# DiverInterfaceBoard.net
KiCad netlist of a schematic drawn in Altium Designer
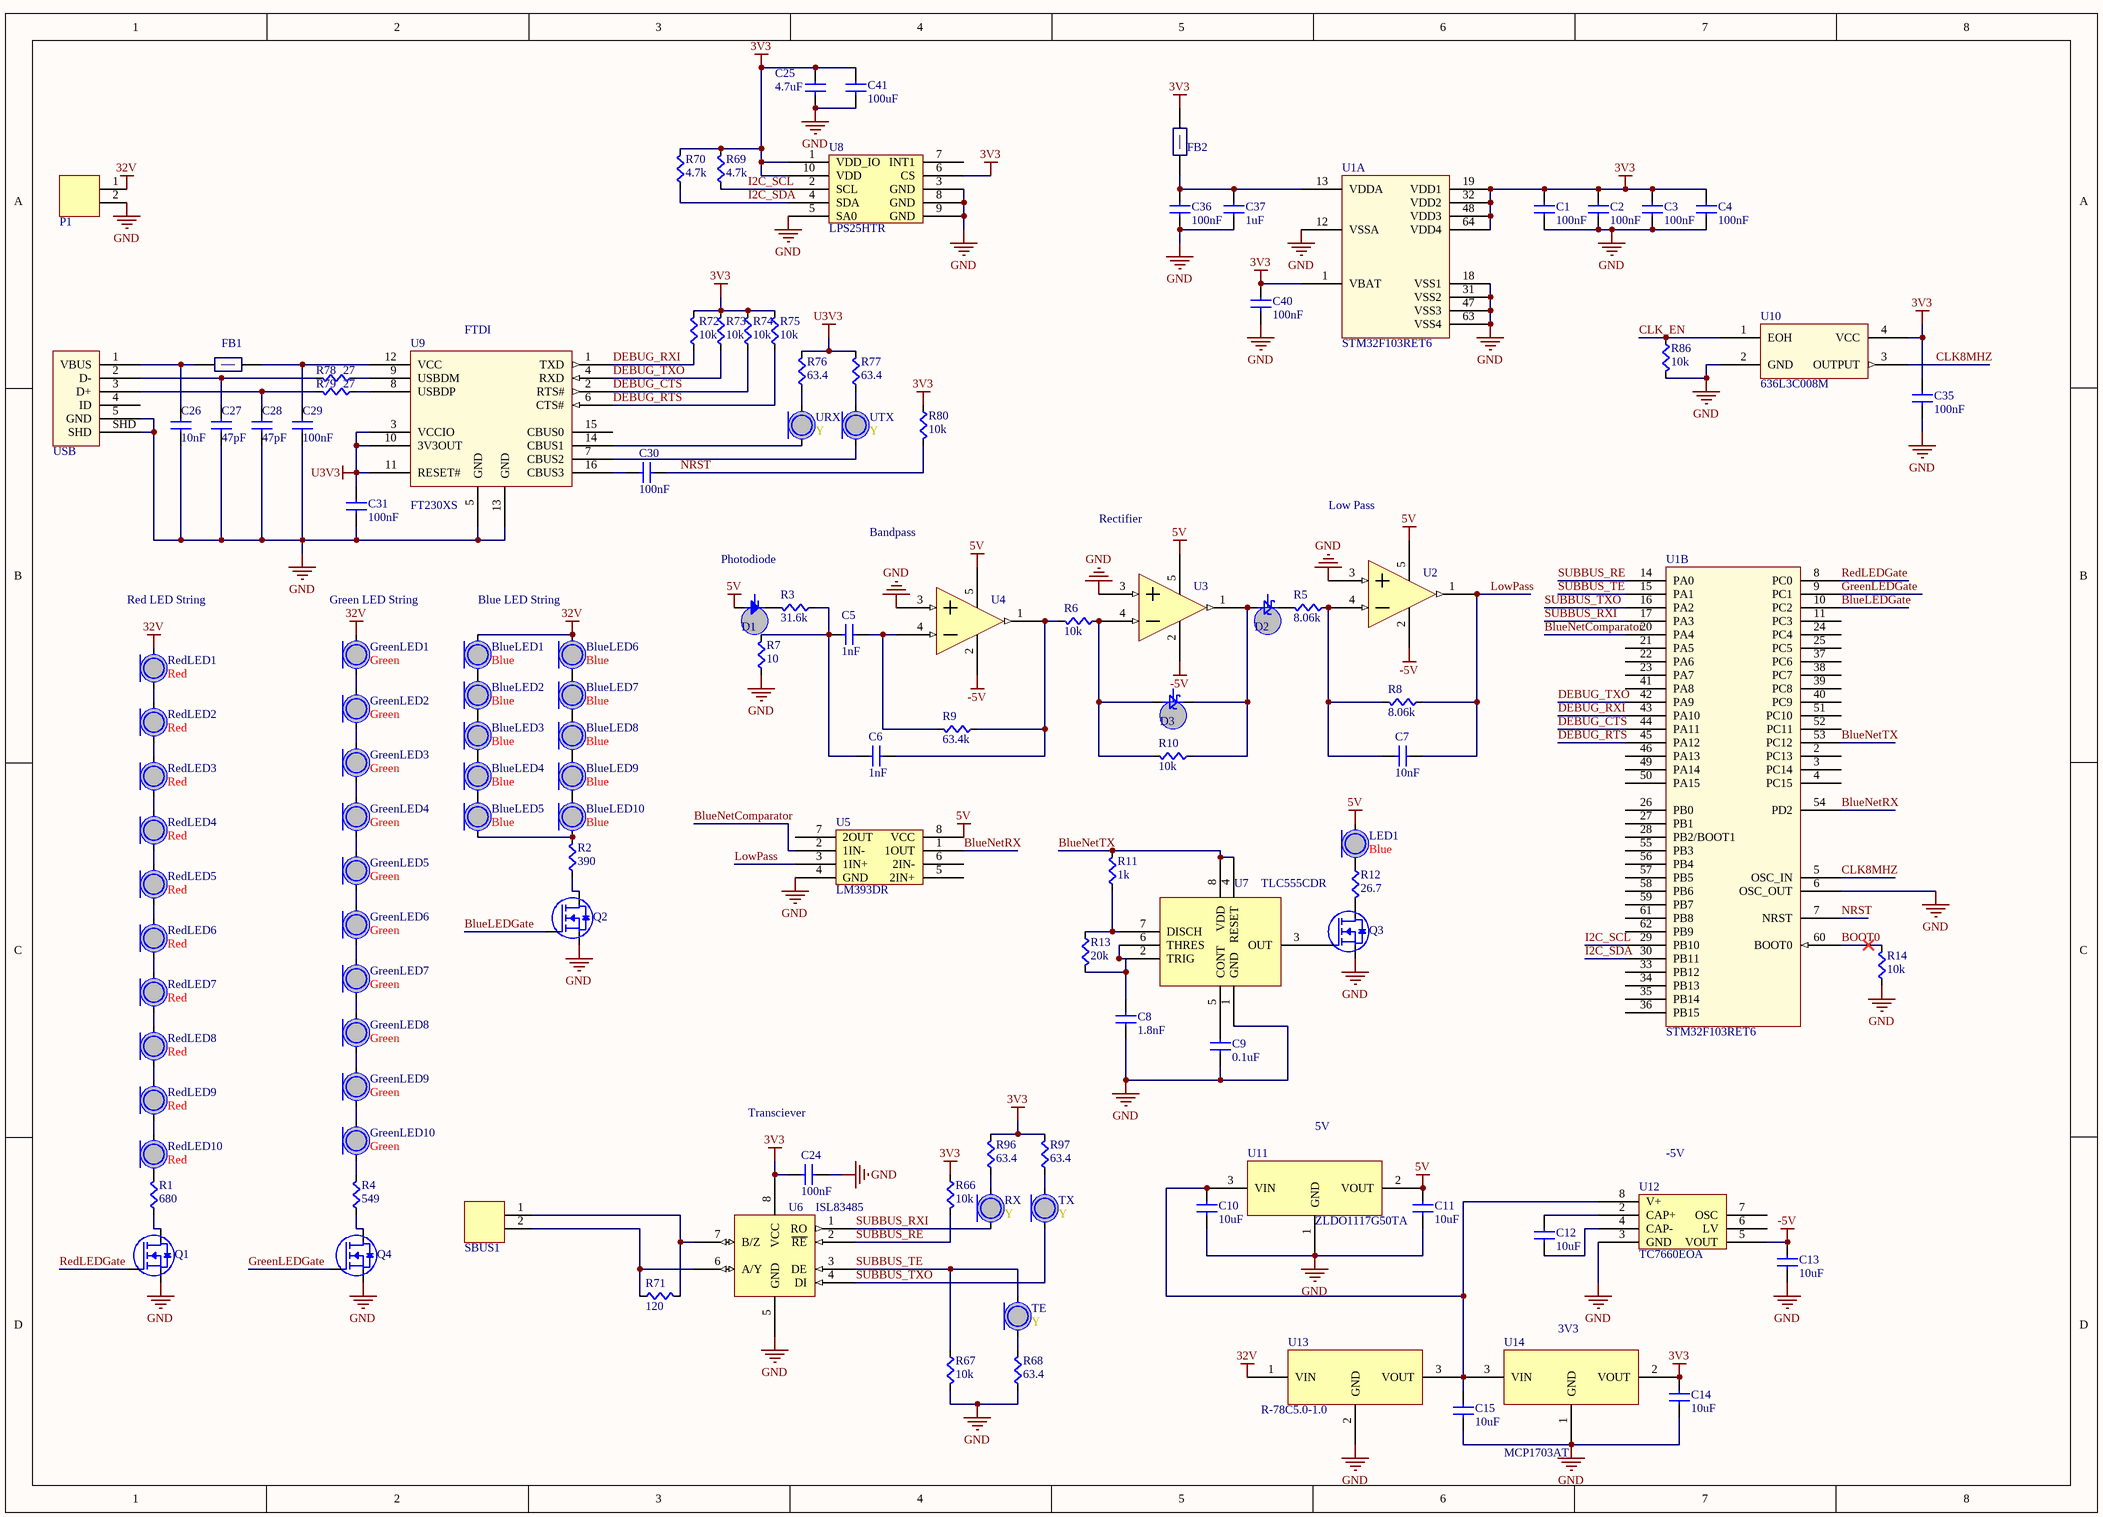
[diagram p0: DiverInterfaceBoard.SchDoc]

(export (version "E")
  (design (tool "Eeschema 10.0.6"))
  (components
    (comp (ref "BlueLED1")
      (value "LED")
      (footprint "LED1206")
      (fields (field (name "COLOR") "Blue"))
      (libsource (lib "SubjuGator8") (part "LED"))
    )
    (comp (ref "BlueLED2")
      (value "LED")
      (footprint "LED1206")
      (fields (field (name "COLOR") "Blue"))
      (libsource (lib "SubjuGator8") (part "LED"))
    )
    (comp (ref "BlueLED3")
      (value "LED")
      (footprint "LED1206")
      (fields (field (name "COLOR") "Blue"))
      (libsource (lib "SubjuGator8") (part "LED"))
    )
    (comp (ref "BlueLED4")
      (value "LED")
      (footprint "LED1206")
      (fields (field (name "COLOR") "Blue"))
      (libsource (lib "SubjuGator8") (part "LED"))
    )
    (comp (ref "BlueLED5")
      (value "LED")
      (footprint "LED1206")
      (fields (field (name "COLOR") "Blue"))
      (libsource (lib "SubjuGator8") (part "LED"))
    )
    (comp (ref "BlueLED6")
      (value "LED")
      (footprint "LED1206")
      (fields (field (name "COLOR") "Blue"))
      (libsource (lib "SubjuGator8") (part "LED"))
    )
    (comp (ref "BlueLED7")
      (value "LED")
      (footprint "LED1206")
      (fields (field (name "COLOR") "Blue"))
      (libsource (lib "SubjuGator8") (part "LED"))
    )
    (comp (ref "BlueLED8")
      (value "LED")
      (footprint "LED1206")
      (fields (field (name "COLOR") "Blue"))
      (libsource (lib "SubjuGator8") (part "LED"))
    )
    (comp (ref "BlueLED9")
      (value "LED")
      (footprint "LED1206")
      (fields (field (name "COLOR") "Blue"))
      (libsource (lib "SubjuGator8") (part "LED"))
    )
    (comp (ref "BlueLED10")
      (value "LED")
      (footprint "LED1206")
      (fields (field (name "COLOR") "Blue"))
      (libsource (lib "SubjuGator8") (part "LED"))
    )
    (comp (ref "C1")
      (value "100nF")
      (footprint "CAPC0603")
      (fields (field (name "Comment") "Cap"))
      (libsource (lib "SubjuGator8") (part "Cap"))
    )
    (comp (ref "C2")
      (value "100nF")
      (footprint "CAPC0603")
      (fields (field (name "Comment") "Cap"))
      (libsource (lib "SubjuGator8") (part "Cap"))
    )
    (comp (ref "C3")
      (value "100nF")
      (footprint "CAPC0603")
      (fields (field (name "Comment") "Cap"))
      (libsource (lib "SubjuGator8") (part "Cap"))
    )
    (comp (ref "C4")
      (value "100nF")
      (footprint "CAPC0603")
      (fields (field (name "Comment") "Cap"))
      (libsource (lib "SubjuGator8") (part "Cap"))
    )
    (comp (ref "C5")
      (value "1nF")
      (footprint "CAPC0603")
      (fields (field (name "Comment") "Cap"))
      (libsource (lib "SubjuGator8") (part "Cap"))
    )
    (comp (ref "C6")
      (value "1nF")
      (footprint "CAPC0603")
      (fields (field (name "Comment") "Cap"))
      (libsource (lib "SubjuGator8") (part "Cap"))
    )
    (comp (ref "C7")
      (value "10nF")
      (footprint "CAPC0603")
      (fields (field (name "Comment") "Cap"))
      (libsource (lib "SubjuGator8") (part "Cap"))
    )
    (comp (ref "C8")
      (value "1.8nF")
      (footprint "CAPC0603")
      (fields (field (name "Comment") "Cap"))
      (libsource (lib "SubjuGator8") (part "Cap"))
    )
    (comp (ref "C9")
      (value "0.1uF")
      (footprint "CAPC0603")
      (fields (field (name "Comment") "Cap"))
      (libsource (lib "SubjuGator8") (part "Cap"))
    )
    (comp (ref "C10")
      (value "10uF")
      (footprint "CAPC0603")
      (fields (field (name "Comment") "Cap"))
      (libsource (lib "SubjuGator8") (part "Cap"))
    )
    (comp (ref "C11")
      (value "10uF")
      (footprint "CAPC0603")
      (fields (field (name "Comment") "Cap"))
      (libsource (lib "SubjuGator8") (part "Cap"))
    )
    (comp (ref "C12")
      (value "10uF")
      (footprint "CAPC0603")
      (fields (field (name "Comment") "Cap"))
      (libsource (lib "SubjuGator8") (part "Cap"))
    )
    (comp (ref "C13")
      (value "10uF")
      (footprint "CAPC0603")
      (fields (field (name "Comment") "Cap"))
      (libsource (lib "SubjuGator8") (part "Cap"))
    )
    (comp (ref "C14")
      (value "10uF")
      (footprint "CAPC0603")
      (fields (field (name "Comment") "Cap"))
      (libsource (lib "SubjuGator8") (part "Cap"))
    )
    (comp (ref "C15")
      (value "10uF")
      (footprint "CAPC0603")
      (fields (field (name "Comment") "Cap"))
      (libsource (lib "SubjuGator8") (part "Cap"))
    )
    (comp (ref "C24")
      (value "100nF")
      (footprint "CAPC0603")
      (fields (field (name "Comment") "Cap"))
      (libsource (lib "SubjuGator8") (part "Cap"))
    )
    (comp (ref "C25")
      (value "4.7uF")
      (footprint "CAPC0603")
      (fields (field (name "Comment") "Cap"))
      (libsource (lib "SubjuGator8") (part "Cap"))
    )
    (comp (ref "C26")
      (value "10nF")
      (footprint "CAPC0603")
      (fields (field (name "Comment") "Cap"))
      (libsource (lib "SubjuGator8") (part "Cap"))
    )
    (comp (ref "C27")
      (value "47pF")
      (footprint "CAPC0603")
      (fields (field (name "Comment") "Cap"))
      (libsource (lib "SubjuGator8") (part "Cap"))
    )
    (comp (ref "C28")
      (value "47pF")
      (footprint "CAPC0603")
      (fields (field (name "Comment") "Cap"))
      (libsource (lib "SubjuGator8") (part "Cap"))
    )
    (comp (ref "C29")
      (value "100nF")
      (footprint "CAPC0603")
      (fields (field (name "Comment") "Cap"))
      (libsource (lib "SubjuGator8") (part "Cap"))
    )
    (comp (ref "C30")
      (value "100nF")
      (footprint "CAPC0603")
      (fields (field (name "Comment") "Cap"))
      (libsource (lib "SubjuGator8") (part "Cap"))
    )
    (comp (ref "C31")
      (value "100nF")
      (footprint "CAPC0603")
      (fields (field (name "Comment") "Cap"))
      (libsource (lib "SubjuGator8") (part "Cap"))
    )
    (comp (ref "C35")
      (value "100nF")
      (footprint "CAPC0603")
      (fields (field (name "Comment") "Cap"))
      (libsource (lib "SubjuGator8") (part "Cap"))
    )
    (comp (ref "C36")
      (value "100nF")
      (footprint "CAPC0603")
      (fields (field (name "Comment") "Cap"))
      (libsource (lib "SubjuGator8") (part "Cap"))
    )
    (comp (ref "C37")
      (value "1uF")
      (footprint "CAPC0603")
      (fields (field (name "Comment") "Cap"))
      (libsource (lib "SubjuGator8") (part "Cap"))
    )
    (comp (ref "C40")
      (value "100nF")
      (footprint "CAPC0603")
      (fields (field (name "MANUFACTURER") "Kemet") (field (name "Comment") "Cap"))
      (libsource (lib "SubjuGator8") (part "Cap"))
    )
    (comp (ref "C41")
      (value "100uF")
      (footprint "CAPC1206")
      (fields (field (name "Comment") "Cap"))
      (libsource (lib "SubjuGator8") (part "Cap"))
    )
    (comp (ref "D1")
      (value "Diode")
      (footprint "TEMD5510FX01")
      (description "Standard Diode Template")
      (libsource (lib "SubjuGator8") (part "Diode"))
    )
    (comp (ref "D2")
      (value "Schottky")
      (footprint "1N5819HW-7-F")
      (description "Schottky Diode Template")
      (libsource (lib "SubjuGator8") (part "Schottky"))
    )
    (comp (ref "D3")
      (value "Schottky")
      (footprint "1N5819HW-7-F")
      (description "Schottky Diode Template")
      (libsource (lib "SubjuGator8") (part "Schottky"))
    )
    (comp (ref "FB1")
      (value "FBead")
      (footprint "RES0603")
      (description "Ferrite Bead")
      (libsource (lib "SubjuGator8") (part "FBead"))
    )
    (comp (ref "FB2")
      (value "FBead")
      (footprint "RES0603")
      (description "Ferrite Bead")
      (libsource (lib "") (part "FBead_1"))
    )
    (comp (ref "GreenLED1")
      (value "LED")
      (footprint "LED1206")
      (fields (field (name "COLOR") "Green"))
      (libsource (lib "SubjuGator8") (part "LED"))
    )
    (comp (ref "GreenLED2")
      (value "LED")
      (footprint "LED1206")
      (fields (field (name "COLOR") "Green"))
      (libsource (lib "SubjuGator8") (part "LED"))
    )
    (comp (ref "GreenLED3")
      (value "LED")
      (footprint "LED1206")
      (fields (field (name "COLOR") "Green"))
      (libsource (lib "SubjuGator8") (part "LED"))
    )
    (comp (ref "GreenLED4")
      (value "LED")
      (footprint "LED1206")
      (fields (field (name "COLOR") "Green"))
      (libsource (lib "SubjuGator8") (part "LED"))
    )
    (comp (ref "GreenLED5")
      (value "LED")
      (footprint "LED1206")
      (fields (field (name "COLOR") "Green"))
      (libsource (lib "SubjuGator8") (part "LED"))
    )
    (comp (ref "GreenLED6")
      (value "LED")
      (footprint "LED1206")
      (fields (field (name "COLOR") "Green"))
      (libsource (lib "SubjuGator8") (part "LED"))
    )
    (comp (ref "GreenLED7")
      (value "LED")
      (footprint "LED1206")
      (fields (field (name "COLOR") "Green"))
      (libsource (lib "SubjuGator8") (part "LED"))
    )
    (comp (ref "GreenLED8")
      (value "LED")
      (footprint "LED1206")
      (fields (field (name "COLOR") "Green"))
      (libsource (lib "SubjuGator8") (part "LED"))
    )
    (comp (ref "GreenLED9")
      (value "LED")
      (footprint "LED1206")
      (fields (field (name "COLOR") "Green"))
      (libsource (lib "SubjuGator8") (part "LED"))
    )
    (comp (ref "GreenLED10")
      (value "LED")
      (footprint "LED1206")
      (fields (field (name "COLOR") "Green"))
      (libsource (lib "SubjuGator8") (part "LED"))
    )
    (comp (ref "LED1")
      (value "LED")
      (footprint "LED0603")
      (fields (field (name "COLOR") "Blue"))
      (libsource (lib "SubjuGator8") (part "LED"))
    )
    (comp (ref "P1")
      (value "2-pin Vert Sherlock")
      (footprint "MOLEX-HDR-1X2-SHERLOCK-VERT")
      (libsource (lib "SubjuGator8") (part "MOLEX-HDR-1x2-SHERLOCK_VERT"))
    )
    (comp (ref "Q1")
      (value "FDN5630")
      (footprint "PowerSOT-3")
      (description "60V N-Channel PowerTrench MOSFET")
      (libsource (lib "SubjuGator8") (part "FDN5630"))
    )
    (comp (ref "Q2")
      (value "FDN5630")
      (footprint "PowerSOT-3")
      (description "60V N-Channel PowerTrench MOSFET")
      (libsource (lib "SubjuGator8") (part "FDN5630"))
    )
    (comp (ref "Q3")
      (value "FDN5630")
      (footprint "PowerSOT-3")
      (description "60V N-Channel PowerTrench MOSFET")
      (libsource (lib "SubjuGator8") (part "FDN5630"))
    )
    (comp (ref "Q4")
      (value "FDN5630")
      (footprint "PowerSOT-3")
      (description "60V N-Channel PowerTrench MOSFET")
      (libsource (lib "SubjuGator8") (part "FDN5630"))
    )
    (comp (ref "R1")
      (value "680")
      (footprint "RES0603")
      (fields (field (name "Comment") "Res"))
      (libsource (lib "SubjuGator8") (part "Res"))
    )
    (comp (ref "R2")
      (value "390")
      (footprint "RES0603")
      (fields (field (name "Comment") "Res"))
      (libsource (lib "SubjuGator8") (part "Res"))
    )
    (comp (ref "R3")
      (value "31.6k")
      (footprint "RES0603")
      (fields (field (name "Comment") "Res"))
      (libsource (lib "SubjuGator8") (part "Res"))
    )
    (comp (ref "R4")
      (value "549")
      (footprint "RES0603")
      (fields (field (name "Comment") "Res"))
      (libsource (lib "SubjuGator8") (part "Res"))
    )
    (comp (ref "R5")
      (value "8.06k")
      (footprint "RES0603")
      (fields (field (name "Comment") "Res"))
      (libsource (lib "SubjuGator8") (part "Res"))
    )
    (comp (ref "R6")
      (value "10k")
      (footprint "RES0603")
      (fields (field (name "Comment") "Res"))
      (libsource (lib "SubjuGator8") (part "Res"))
    )
    (comp (ref "R7")
      (value "10")
      (footprint "RES0603")
      (fields (field (name "Comment") "Res"))
      (libsource (lib "SubjuGator8") (part "Res"))
    )
    (comp (ref "R8")
      (value "8.06k")
      (footprint "RES0603")
      (fields (field (name "Comment") "Res"))
      (libsource (lib "SubjuGator8") (part "Res"))
    )
    (comp (ref "R9")
      (value "63.4k")
      (footprint "RES0603")
      (fields (field (name "Comment") "Res"))
      (libsource (lib "SubjuGator8") (part "Res"))
    )
    (comp (ref "R10")
      (value "10k")
      (footprint "RES0603")
      (fields (field (name "Comment") "Res"))
      (libsource (lib "SubjuGator8") (part "Res"))
    )
    (comp (ref "R11")
      (value "1k")
      (footprint "RES0603")
      (fields (field (name "Comment") "Res"))
      (libsource (lib "SubjuGator8") (part "Res"))
    )
    (comp (ref "R12")
      (value "26.7")
      (footprint "RES0603")
      (fields (field (name "Comment") "Res"))
      (libsource (lib "SubjuGator8") (part "Res"))
    )
    (comp (ref "R13")
      (value "20k")
      (footprint "RES0603")
      (fields (field (name "Comment") "Res"))
      (libsource (lib "SubjuGator8") (part "Res"))
    )
    (comp (ref "R14")
      (value "10k")
      (footprint "RES0603")
      (fields (field (name "Comment") "Res"))
      (libsource (lib "SubjuGator8") (part "Res"))
    )
    (comp (ref "R66")
      (value "10k")
      (footprint "RES0603")
      (fields (field (name "Comment") "Res"))
      (libsource (lib "SubjuGator8") (part "Res"))
    )
    (comp (ref "R67")
      (value "10k")
      (footprint "RES0603")
      (fields (field (name "Comment") "Res"))
      (libsource (lib "SubjuGator8") (part "Res"))
    )
    (comp (ref "R68")
      (value "63.4")
      (footprint "RES0603")
      (fields (field (name "Comment") "Res"))
      (libsource (lib "SubjuGator8") (part "Res"))
    )
    (comp (ref "R69")
      (value "4.7k")
      (footprint "RES0603")
      (fields (field (name "Comment") "Res"))
      (libsource (lib "SubjuGator8") (part "Res"))
    )
    (comp (ref "R70")
      (value "4.7k")
      (footprint "RES0603")
      (fields (field (name "Comment") "Res"))
      (libsource (lib "SubjuGator8") (part "Res"))
    )
    (comp (ref "R71")
      (value "120")
      (footprint "RES0603")
      (fields (field (name "Comment") "Res"))
      (libsource (lib "SubjuGator8") (part "Res"))
    )
    (comp (ref "R72")
      (value "10k")
      (footprint "RES0603")
      (fields (field (name "Comment") "Res"))
      (libsource (lib "SubjuGator8") (part "Res"))
    )
    (comp (ref "R73")
      (value "10k")
      (footprint "RES0603")
      (fields (field (name "Comment") "Res"))
      (libsource (lib "SubjuGator8") (part "Res"))
    )
    (comp (ref "R74")
      (value "10k")
      (footprint "RES0603")
      (fields (field (name "Comment") "Res"))
      (libsource (lib "SubjuGator8") (part "Res"))
    )
    (comp (ref "R75")
      (value "10k")
      (footprint "RES0603")
      (fields (field (name "Comment") "Res"))
      (libsource (lib "SubjuGator8") (part "Res"))
    )
    (comp (ref "R76")
      (value "63.4")
      (footprint "RES0603")
      (fields (field (name "Comment") "Res"))
      (libsource (lib "SubjuGator8") (part "Res"))
    )
    (comp (ref "R77")
      (value "63.4")
      (footprint "RES0603")
      (fields (field (name "Comment") "Res"))
      (libsource (lib "SubjuGator8") (part "Res"))
    )
    (comp (ref "R78")
      (value "27")
      (footprint "RES0603")
      (fields (field (name "Comment") "Res"))
      (libsource (lib "SubjuGator8") (part "Res"))
    )
    (comp (ref "R79")
      (value "27")
      (footprint "RES0603")
      (fields (field (name "Comment") "Res"))
      (libsource (lib "SubjuGator8") (part "Res"))
    )
    (comp (ref "R80")
      (value "10k")
      (footprint "RES0603")
      (fields (field (name "Comment") "Res"))
      (libsource (lib "SubjuGator8") (part "Res"))
    )
    (comp (ref "R86")
      (value "10k")
      (footprint "RES0603")
      (fields (field (name "Comment") "Res"))
      (libsource (lib "SubjuGator8") (part "Res"))
    )
    (comp (ref "R96")
      (value "63.4")
      (footprint "RES0603")
      (fields (field (name "Comment") "Res"))
      (libsource (lib "SubjuGator8") (part "Res"))
    )
    (comp (ref "R97")
      (value "63.4")
      (footprint "RES0603")
      (fields (field (name "Comment") "Res"))
      (libsource (lib "SubjuGator8") (part "Res"))
    )
    (comp (ref "RedLED1")
      (value "LED")
      (footprint "LED1206")
      (fields (field (name "COLOR") "Red"))
      (libsource (lib "SubjuGator8") (part "LED"))
    )
    (comp (ref "RedLED2")
      (value "LED")
      (footprint "LED1206")
      (fields (field (name "COLOR") "Red"))
      (libsource (lib "SubjuGator8") (part "LED"))
    )
    (comp (ref "RedLED3")
      (value "LED")
      (footprint "LED1206")
      (fields (field (name "COLOR") "Red"))
      (libsource (lib "SubjuGator8") (part "LED"))
    )
    (comp (ref "RedLED4")
      (value "LED")
      (footprint "LED1206")
      (fields (field (name "COLOR") "Red"))
      (libsource (lib "SubjuGator8") (part "LED"))
    )
    (comp (ref "RedLED5")
      (value "LED")
      (footprint "LED1206")
      (fields (field (name "COLOR") "Red"))
      (libsource (lib "SubjuGator8") (part "LED"))
    )
    (comp (ref "RedLED6")
      (value "LED")
      (footprint "LED1206")
      (fields (field (name "COLOR") "Red"))
      (libsource (lib "SubjuGator8") (part "LED"))
    )
    (comp (ref "RedLED7")
      (value "LED")
      (footprint "LED1206")
      (fields (field (name "COLOR") "Red"))
      (libsource (lib "SubjuGator8") (part "LED"))
    )
    (comp (ref "RedLED8")
      (value "LED")
      (footprint "LED1206")
      (fields (field (name "COLOR") "Red"))
      (libsource (lib "SubjuGator8") (part "LED"))
    )
    (comp (ref "RedLED9")
      (value "LED")
      (footprint "LED1206")
      (fields (field (name "COLOR") "Red"))
      (libsource (lib "SubjuGator8") (part "LED"))
    )
    (comp (ref "RedLED10")
      (value "LED")
      (footprint "LED1206")
      (fields (field (name "COLOR") "Red"))
      (libsource (lib "SubjuGator8") (part "LED"))
    )
    (comp (ref "RX")
      (value "LED")
      (footprint "LED0805")
      (fields (field (name "COLOR") "Y"))
      (libsource (lib "SubjuGator8") (part "LED"))
    )
    (comp (ref "SBUS1")
      (value "2-pin Horz Sherlock")
      (footprint "MOLEX-HDR-1X2-SHERLOCK-HORZ")
      (fields
        (field (name "MANUFACTURER PART NUMBER") "0353630260")
        (field (name "MANUFACTURER") "Molex Inc")
      )
      (libsource (lib "SubjuGator8") (part "MOLEX-HDR-1x2-SHERLOCK_RA"))
    )
    (comp (ref "TE")
      (value "LED")
      (footprint "LED0805")
      (fields (field (name "COLOR") "Y"))
      (libsource (lib "SubjuGator8") (part "LED"))
    )
    (comp (ref "TX")
      (value "LED")
      (footprint "LED0805")
      (fields (field (name "COLOR") "Y"))
      (libsource (lib "SubjuGator8") (part "LED"))
    )
    (comp (ref "U1")
      (value "STM32F103RET6")
      (footprint "STM32F103RxTx")
      (description "Mainstream Performance line, ARM Cortex-M3 MCU")
      (libsource (lib "SubjuGator8") (part "STM32F103RET6"))
    )
    (comp (ref "U2")
      (value "MCP6L01")
      (footprint "MCP6L01R")
      (description "Op Amp Rail-to-Rail 1Mhz")
      (libsource (lib "SubjuGator8") (part "MCP6L01"))
    )
    (comp (ref "U3")
      (value "MCP6L01")
      (footprint "MCP6L01R")
      (description "Op Amp Rail-to-Rail 1Mhz")
      (libsource (lib "SubjuGator8") (part "MCP6L01"))
    )
    (comp (ref "U4")
      (value "MCP6L01")
      (footprint "MCP6L01R")
      (description "Op Amp Rail-to-Rail 1Mhz")
      (libsource (lib "SubjuGator8") (part "MCP6L01"))
    )
    (comp (ref "U5")
      (value "LM393DR")
      (footprint "LM393DR")
      (description "LM393DR Comparator")
      (libsource (lib "SubjuGator8") (part "LM393DR"))
    )
    (comp (ref "U6")
      (value "ISL83485")
      (footprint "ISL8348xIBZ")
      (description "3.3V RS485 Transceiver")
      (libsource (lib "SubjuGator8") (part "ISL83485"))
    )
    (comp (ref "U7")
      (value "TLC555CDR")
      (footprint "TLC555CDR")
      (description "IC OSC MONO TIMING 2.1MHZ 8-SOIC")
      (libsource (lib "SubjuGator8") (part "TLC555CDR"))
    )
    (comp (ref "U8")
      (value "LPS25HTR")
      (footprint "LPS25HTR")
      (description "IC MEMS PRESSURE SENSOR 10HCLGA")
      (libsource (lib "SubjuGator8") (part "LPS25HTR"))
    )
    (comp (ref "U9")
      (value "FT230XS")
      (footprint "FT230XS")
      (description "USB To Basic UART IC")
      (libsource (lib "SubjuGator8") (part "FT230XS"))
    )
    (comp (ref "U10")
      (value "636L3C008M")
      (footprint "636L3C")
      (description "HCMOS/TTL Clock Oscillator")
      (libsource (lib "SubjuGator8") (part "636L3C"))
    )
    (comp (ref "U11")
      (value "ZLDO1117G50TA")
      (footprint "ZLDO1117G50TA")
      (description "IC REG LDO 5V 1A SOT223-3")
      (libsource (lib "SubjuGator8") (part "ZLDO1117G50TA"))
    )
    (comp (ref "U12")
      (value "TC7660EOA")
      (footprint "TC7660EOA")
      (description "IC REG SWITCHD CAP INV ADJ 8SOIC")
      (libsource (lib "SubjuGator8") (part "TC7660EOA"))
    )
    (comp (ref "U13")
      (value "R-78C5.0-1.0")
      (footprint "R-78C5.0-1.0")
      (description "CONV DC/DC 1A 5V OUT SIP VERT")
      (libsource (lib "SubjuGator8") (part "R-78C5.0-1.0"))
    )
    (comp (ref "U14")
      (value "MCP1703AT")
      (footprint "MCP1703AT-xx02EDB")
      (description "250 mA, 16V, Low Quiescent Current LDO Regulator")
      (libsource (lib "SubjuGator8") (part "MCP1703AT"))
    )
    (comp (ref "URX")
      (value "LED")
      (footprint "LED0805")
      (fields (field (name "COLOR") "Y"))
      (libsource (lib "SubjuGator8") (part "LED"))
    )
    (comp (ref "USB")
      (value "UX60SC-MB-5ST")
      (footprint "UX60SC-MB-5ST")
      (description "USB Mini B Metal Shield SMT")
      (libsource (lib "SubjuGator8") (part "UX60SC-MB-5ST"))
    )
    (comp (ref "UTX")
      (value "LED")
      (footprint "LED0805")
      (fields (field (name "COLOR") "Y"))
      (libsource (lib "SubjuGator8") (part "LED"))
    )
  )
  (nets
    (net (code "1") (name "-5V") (class "Default")
      (node (ref "C13") (pin "1") (pinfunction "A_1") (pintype "passive"))
      (node (ref "U12") (pin "5") (pinfunction "VOUT_5") (pintype "passive"))
      (node (ref "U2") (pin "2") (pinfunction "VSS_2") (pintype "power_in"))
      (node (ref "U3") (pin "2") (pinfunction "VSS_2") (pintype "power_in"))
      (node (ref "U4") (pin "2") (pinfunction "VSS_2") (pintype "power_in"))
    )
    (net (code "2") (name "/BOOT0") (class "Default")
      (node (ref "R14") (pin "1") (pinfunction "A_1") (pintype "passive"))
      (node (ref "U1") (pin "60") (pinfunction "BOOT0_60") (pintype "input"))
    )
    (net (code "3") (name "/BlueLEDGate") (class "Default")
      (node (ref "Q2") (pin "G") (pinfunction "G_G") (pintype "passive"))
      (node (ref "U1") (pin "10") (pinfunction "PC2_10") (pintype "passive"))
    )
    (net (code "4") (name "/BlueNetComparator") (class "Default")
      (node (ref "U1") (pin "20") (pinfunction "PA4_20") (pintype "passive"))
      (node (ref "U5") (pin "2") (pinfunction "1IN-_2") (pintype "passive"))
    )
    (net (code "5") (name "/BlueNetRX") (class "Default")
      (node (ref "U1") (pin "54") (pinfunction "PD2_54") (pintype "passive"))
      (node (ref "U5") (pin "1") (pinfunction "1OUT_1") (pintype "passive"))
    )
    (net (code "6") (name "/BlueNetTX") (class "Default")
      (node (ref "R11") (pin "1") (pinfunction "A_1") (pintype "passive"))
      (node (ref "U1") (pin "53") (pinfunction "PC12_53") (pintype "passive"))
      (node (ref "U7") (pin "4") (pinfunction "RESET_4") (pintype "passive"))
      (node (ref "U7") (pin "8") (pinfunction "VDD_8") (pintype "passive"))
    )
    (net (code "7") (name "/CLK8MHZ") (class "Default")
      (node (ref "U1") (pin "5") (pinfunction "OSC_IN_5") (pintype "passive"))
      (node (ref "U10") (pin "3") (pinfunction "OUTPUT_3") (pintype "output"))
    )
    (net (code "8") (name "/CLK_EN") (class "Default")
      (node (ref "R86") (pin "2") (pinfunction "B_2") (pintype "passive"))
      (node (ref "U10") (pin "1") (pinfunction "EOH_1") (pintype "passive"))
    )
    (net (code "9") (name "/DEBUG_CTS") (class "Default")
      (node (ref "R74") (pin "2") (pinfunction "B_2") (pintype "passive"))
      (node (ref "U1") (pin "44") (pinfunction "PA11_44") (pintype "passive"))
      (node (ref "U9") (pin "2") (pinfunction "RTS#_2") (pintype "output"))
    )
    (net (code "10") (name "/DEBUG_RTS") (class "Default")
      (node (ref "R75") (pin "2") (pinfunction "B_2") (pintype "passive"))
      (node (ref "U1") (pin "45") (pinfunction "PA12_45") (pintype "passive"))
      (node (ref "U9") (pin "6") (pinfunction "CTS#_6") (pintype "input"))
    )
    (net (code "11") (name "/DEBUG_RXI") (class "Default")
      (node (ref "R72") (pin "2") (pinfunction "B_2") (pintype "passive"))
      (node (ref "U1") (pin "43") (pinfunction "PA10_43") (pintype "passive"))
      (node (ref "U9") (pin "1") (pinfunction "TXD_1") (pintype "output"))
    )
    (net (code "12") (name "/DEBUG_TXO") (class "Default")
      (node (ref "R73") (pin "2") (pinfunction "B_2") (pintype "passive"))
      (node (ref "U1") (pin "42") (pinfunction "PA9_42") (pintype "passive"))
      (node (ref "U9") (pin "4") (pinfunction "RXD_4") (pintype "input"))
    )
    (net (code "13") (name "/GreenLEDGate") (class "Default")
      (node (ref "Q4") (pin "G") (pinfunction "G_G") (pintype "passive"))
      (node (ref "U1") (pin "9") (pinfunction "PC1_9") (pintype "passive"))
    )
    (net (code "14") (name "/I2C_SCL") (class "Default")
      (node (ref "R69") (pin "2") (pinfunction "B_2") (pintype "passive"))
      (node (ref "U1") (pin "29") (pinfunction "PB10_29") (pintype "passive"))
      (node (ref "U8") (pin "2") (pinfunction "SCL_2") (pintype "passive"))
    )
    (net (code "15") (name "/I2C_SDA") (class "Default")
      (node (ref "R70") (pin "2") (pinfunction "B_2") (pintype "passive"))
      (node (ref "U1") (pin "30") (pinfunction "PB11_30") (pintype "passive"))
      (node (ref "U8") (pin "4") (pinfunction "SDA_4") (pintype "passive"))
    )
    (net (code "16") (name "/LowPass") (class "Default")
      (node (ref "C7") (pin "2") (pinfunction "B_2") (pintype "passive"))
      (node (ref "R8") (pin "2") (pinfunction "B_2") (pintype "passive"))
      (node (ref "U2") (pin "1") (pinfunction "VOUT_1") (pintype "output"))
      (node (ref "U5") (pin "3") (pinfunction "1IN+_3") (pintype "passive"))
    )
    (net (code "17") (name "/NRST") (class "Default")
      (node (ref "C30") (pin "2") (pinfunction "B_2") (pintype "passive"))
      (node (ref "R80") (pin "2") (pinfunction "B_2") (pintype "passive"))
      (node (ref "U1") (pin "7") (pinfunction "NRST_7") (pintype "passive"))
    )
    (net (code "18") (name "/RedLEDGate") (class "Default")
      (node (ref "Q1") (pin "G") (pinfunction "G_G") (pintype "passive"))
      (node (ref "U1") (pin "8") (pinfunction "PC0_8") (pintype "passive"))
    )
    (net (code "19") (name "/SUBBUS_RE") (class "Default")
      (node (ref "R66") (pin "2") (pinfunction "B_2") (pintype "passive"))
      (node (ref "U1") (pin "14") (pinfunction "PA0_14") (pintype "passive"))
      (node (ref "U6") (pin "2") (pinfunction "~{RE}_2") (pintype "input"))
    )
    (net (code "20") (name "/SUBBUS_RXI") (class "Default")
      (node (ref "RX") (pin "C") (pinfunction "C_C") (pintype "passive"))
      (node (ref "U1") (pin "17") (pinfunction "PA3_17") (pintype "passive"))
      (node (ref "U6") (pin "1") (pinfunction "RO_1") (pintype "output"))
    )
    (net (code "21") (name "/SUBBUS_TE") (class "Default")
      (node (ref "R67") (pin "1") (pinfunction "A_1") (pintype "passive"))
      (node (ref "TE") (pin "A") (pinfunction "A_A") (pintype "passive"))
      (node (ref "U1") (pin "15") (pinfunction "PA1_15") (pintype "passive"))
      (node (ref "U6") (pin "3") (pinfunction "DE_3") (pintype "input"))
    )
    (net (code "22") (name "/SUBBUS_TXO") (class "Default")
      (node (ref "TX") (pin "C") (pinfunction "C_C") (pintype "passive"))
      (node (ref "U1") (pin "16") (pinfunction "PA2_16") (pintype "passive"))
      (node (ref "U6") (pin "4") (pinfunction "DI_4") (pintype "input"))
    )
    (net (code "23") (name "3V3") (class "Default")
      (node (ref "C1") (pin "1") (pinfunction "A_1") (pintype "passive"))
      (node (ref "C14") (pin "1") (pinfunction "A_1") (pintype "passive"))
      (node (ref "C2") (pin "1") (pinfunction "A_1") (pintype "passive"))
      (node (ref "C24") (pin "2") (pinfunction "B_2") (pintype "passive"))
      (node (ref "C25") (pin "1") (pinfunction "A_1") (pintype "passive"))
      (node (ref "C3") (pin "1") (pinfunction "A_1") (pintype "passive"))
      (node (ref "C35") (pin "1") (pinfunction "A_1") (pintype "passive"))
      (node (ref "C4") (pin "1") (pinfunction "A_1") (pintype "passive"))
      (node (ref "C40") (pin "1") (pinfunction "A_1") (pintype "passive"))
      (node (ref "C41") (pin "1") (pinfunction "A_1") (pintype "passive"))
      (node (ref "FB2") (pin "2") (pinfunction "B_2") (pintype "passive"))
      (node (ref "R66") (pin "1") (pinfunction "A_1") (pintype "passive"))
      (node (ref "R69") (pin "1") (pinfunction "A_1") (pintype "passive"))
      (node (ref "R70") (pin "1") (pinfunction "A_1") (pintype "passive"))
      (node (ref "R72") (pin "1") (pinfunction "A_1") (pintype "passive"))
      (node (ref "R73") (pin "1") (pinfunction "A_1") (pintype "passive"))
      (node (ref "R74") (pin "1") (pinfunction "A_1") (pintype "passive"))
      (node (ref "R75") (pin "1") (pinfunction "A_1") (pintype "passive"))
      (node (ref "R80") (pin "1") (pinfunction "A_1") (pintype "passive"))
      (node (ref "R96") (pin "1") (pinfunction "A_1") (pintype "passive"))
      (node (ref "R97") (pin "1") (pinfunction "A_1") (pintype "passive"))
      (node (ref "U1") (pin "1") (pinfunction "VBAT_1") (pintype "power_in"))
      (node (ref "U1") (pin "19") (pinfunction "VDD1_19") (pintype "power_in"))
      (node (ref "U1") (pin "32") (pinfunction "VDD2_32") (pintype "power_in"))
      (node (ref "U1") (pin "48") (pinfunction "VDD3_48") (pintype "power_in"))
      (node (ref "U1") (pin "64") (pinfunction "VDD4_64") (pintype "power_in"))
      (node (ref "U10") (pin "4") (pinfunction "VCC_4") (pintype "power_in"))
      (node (ref "U14") (pin "2") (pinfunction "VOUT_2") (pintype "passive"))
      (node (ref "U6") (pin "8") (pinfunction "VCC_8") (pintype "power_in"))
      (node (ref "U8") (pin "1") (pinfunction "VDD_IO_1") (pintype "passive"))
      (node (ref "U8") (pin "10") (pinfunction "VDD_10") (pintype "passive"))
      (node (ref "U8") (pin "6") (pinfunction "CS_6") (pintype "passive"))
    )
    (net (code "24") (name "5V") (class "Default")
      (node (ref "C11") (pin "1") (pinfunction "A_1") (pintype "passive"))
      (node (ref "D1") (pin "A") (pinfunction "A_A") (pintype "passive"))
      (node (ref "LED1") (pin "A") (pinfunction "A_A") (pintype "passive"))
      (node (ref "U11") (pin "2") (pinfunction "VOUT_2") (pintype "passive"))
      (node (ref "U2") (pin "5") (pinfunction "VDD_5") (pintype "power_in"))
      (node (ref "U3") (pin "5") (pinfunction "VDD_5") (pintype "power_in"))
      (node (ref "U4") (pin "5") (pinfunction "VDD_5") (pintype "power_in"))
      (node (ref "U5") (pin "8") (pinfunction "VCC_8") (pintype "passive"))
    )
    (net (code "25") (name "32V") (class "Default")
      (node (ref "BlueLED1") (pin "A") (pinfunction "A_A") (pintype "passive"))
      (node (ref "BlueLED6") (pin "A") (pinfunction "A_A") (pintype "passive"))
      (node (ref "GreenLED1") (pin "A") (pinfunction "A_A") (pintype "passive"))
      (node (ref "P1") (pin "1") (pinfunction "1_1") (pintype "passive"))
      (node (ref "RedLED1") (pin "A") (pinfunction "A_A") (pintype "passive"))
      (node (ref "U13") (pin "1") (pinfunction "VIN_1") (pintype "passive"))
    )
    (net (code "26") (name "GND") (class "Default")
      (node (ref "C1") (pin "2") (pinfunction "B_2") (pintype "passive"))
      (node (ref "C10") (pin "2") (pinfunction "B_2") (pintype "passive"))
      (node (ref "C11") (pin "2") (pinfunction "B_2") (pintype "passive"))
      (node (ref "C13") (pin "2") (pinfunction "B_2") (pintype "passive"))
      (node (ref "C14") (pin "2") (pinfunction "B_2") (pintype "passive"))
      (node (ref "C15") (pin "2") (pinfunction "B_2") (pintype "passive"))
      (node (ref "C2") (pin "2") (pinfunction "B_2") (pintype "passive"))
      (node (ref "C24") (pin "1") (pinfunction "A_1") (pintype "passive"))
      (node (ref "C25") (pin "2") (pinfunction "B_2") (pintype "passive"))
      (node (ref "C26") (pin "2") (pinfunction "B_2") (pintype "passive"))
      (node (ref "C27") (pin "2") (pinfunction "B_2") (pintype "passive"))
      (node (ref "C28") (pin "2") (pinfunction "B_2") (pintype "passive"))
      (node (ref "C29") (pin "2") (pinfunction "B_2") (pintype "passive"))
      (node (ref "C3") (pin "2") (pinfunction "B_2") (pintype "passive"))
      (node (ref "C31") (pin "2") (pinfunction "B_2") (pintype "passive"))
      (node (ref "C35") (pin "2") (pinfunction "B_2") (pintype "passive"))
      (node (ref "C36") (pin "2") (pinfunction "B_2") (pintype "passive"))
      (node (ref "C37") (pin "2") (pinfunction "B_2") (pintype "passive"))
      (node (ref "C4") (pin "2") (pinfunction "B_2") (pintype "passive"))
      (node (ref "C40") (pin "2") (pinfunction "B_2") (pintype "passive"))
      (node (ref "C41") (pin "2") (pinfunction "B_2") (pintype "passive"))
      (node (ref "C8") (pin "2") (pinfunction "B_2") (pintype "passive"))
      (node (ref "C9") (pin "2") (pinfunction "B_2") (pintype "passive"))
      (node (ref "P1") (pin "2") (pinfunction "2_2") (pintype "passive"))
      (node (ref "Q1") (pin "S") (pinfunction "S_S") (pintype "passive"))
      (node (ref "Q2") (pin "S") (pinfunction "S_S") (pintype "passive"))
      (node (ref "Q3") (pin "S") (pinfunction "S_S") (pintype "passive"))
      (node (ref "Q4") (pin "S") (pinfunction "S_S") (pintype "passive"))
      (node (ref "R14") (pin "2") (pinfunction "B_2") (pintype "passive"))
      (node (ref "R67") (pin "2") (pinfunction "B_2") (pintype "passive"))
      (node (ref "R68") (pin "2") (pinfunction "B_2") (pintype "passive"))
      (node (ref "R7") (pin "2") (pinfunction "B_2") (pintype "passive"))
      (node (ref "R86") (pin "1") (pinfunction "A_1") (pintype "passive"))
      (node (ref "U1") (pin "12") (pinfunction "VSSA_12") (pintype "power_in"))
      (node (ref "U1") (pin "18") (pinfunction "VSS1_18") (pintype "power_in"))
      (node (ref "U1") (pin "31") (pinfunction "VSS2_31") (pintype "power_in"))
      (node (ref "U1") (pin "47") (pinfunction "VSS3_47") (pintype "power_in"))
      (node (ref "U1") (pin "6") (pinfunction "OSC_OUT_6") (pintype "passive"))
      (node (ref "U1") (pin "63") (pinfunction "VSS4_63") (pintype "power_in"))
      (node (ref "U10") (pin "2") (pinfunction "GND_2") (pintype "power_in"))
      (node (ref "U11") (pin "1") (pinfunction "GND_1") (pintype "power_in"))
      (node (ref "U12") (pin "3") (pinfunction "GND_3") (pintype "passive"))
      (node (ref "U13") (pin "2") (pinfunction "GND_2") (pintype "power_in"))
      (node (ref "U14") (pin "1") (pinfunction "GND_1") (pintype "power_in"))
      (node (ref "U2") (pin "3") (pinfunction "VIN+_3") (pintype "input"))
      (node (ref "U3") (pin "3") (pinfunction "VIN+_3") (pintype "input"))
      (node (ref "U4") (pin "3") (pinfunction "VIN+_3") (pintype "input"))
      (node (ref "U5") (pin "4") (pinfunction "GND_4") (pintype "passive"))
      (node (ref "U6") (pin "5") (pinfunction "GND_5") (pintype "power_in"))
      (node (ref "U7") (pin "1") (pinfunction "GND_1") (pintype "passive"))
      (node (ref "U8") (pin "3") (pinfunction "GND_3") (pintype "passive"))
      (node (ref "U8") (pin "5") (pinfunction "SA0_5") (pintype "passive"))
      (node (ref "U8") (pin "8") (pinfunction "GND_8") (pintype "passive"))
      (node (ref "U8") (pin "9") (pinfunction "GND_9") (pintype "passive"))
      (node (ref "U9") (pin "13") (pinfunction "GND_13") (pintype "power_in"))
      (node (ref "U9") (pin "5") (pinfunction "GND_5") (pintype "power_in"))
      (node (ref "USB") (pin "5") (pinfunction "GND_5") (pintype "passive"))
      (node (ref "USB") (pin "SHD") (pinfunction "SHD_SHD") (pintype "passive"))
    )
    (net (code "27") (name "Net-(BlueLED1-PadC)") (class "Default")
      (node (ref "BlueLED1") (pin "C") (pinfunction "C_C") (pintype "passive"))
      (node (ref "BlueLED2") (pin "A") (pinfunction "A_A") (pintype "passive"))
    )
    (net (code "28") (name "Net-(BlueLED2-PadC)") (class "Default")
      (node (ref "BlueLED2") (pin "C") (pinfunction "C_C") (pintype "passive"))
      (node (ref "BlueLED3") (pin "A") (pinfunction "A_A") (pintype "passive"))
    )
    (net (code "29") (name "Net-(BlueLED3-PadC)") (class "Default")
      (node (ref "BlueLED3") (pin "C") (pinfunction "C_C") (pintype "passive"))
      (node (ref "BlueLED4") (pin "A") (pinfunction "A_A") (pintype "passive"))
    )
    (net (code "30") (name "Net-(BlueLED4-PadC)") (class "Default")
      (node (ref "BlueLED4") (pin "C") (pinfunction "C_C") (pintype "passive"))
      (node (ref "BlueLED5") (pin "A") (pinfunction "A_A") (pintype "passive"))
    )
    (net (code "31") (name "Net-(BlueLED6-PadC)") (class "Default")
      (node (ref "BlueLED6") (pin "C") (pinfunction "C_C") (pintype "passive"))
      (node (ref "BlueLED7") (pin "A") (pinfunction "A_A") (pintype "passive"))
    )
    (net (code "32") (name "Net-(BlueLED7-PadC)") (class "Default")
      (node (ref "BlueLED7") (pin "C") (pinfunction "C_C") (pintype "passive"))
      (node (ref "BlueLED8") (pin "A") (pinfunction "A_A") (pintype "passive"))
    )
    (net (code "33") (name "Net-(BlueLED8-PadC)") (class "Default")
      (node (ref "BlueLED8") (pin "C") (pinfunction "C_C") (pintype "passive"))
      (node (ref "BlueLED9") (pin "A") (pinfunction "A_A") (pintype "passive"))
    )
    (net (code "34") (name "Net-(BlueLED10-PadA)") (class "Default")
      (node (ref "BlueLED10") (pin "A") (pinfunction "A_A") (pintype "passive"))
      (node (ref "BlueLED9") (pin "C") (pinfunction "C_C") (pintype "passive"))
    )
    (net (code "35") (name "Net-(C5-A)") (class "Default")
      (node (ref "C5") (pin "1") (pinfunction "A_1") (pintype "passive"))
      (node (ref "C6") (pin "1") (pinfunction "A_1") (pintype "passive"))
      (node (ref "R3") (pin "2") (pinfunction "B_2") (pintype "passive"))
      (node (ref "R7") (pin "1") (pinfunction "A_1") (pintype "passive"))
    )
    (net (code "36") (name "Net-(C5-B)") (class "Default")
      (node (ref "C5") (pin "2") (pinfunction "B_2") (pintype "passive"))
      (node (ref "R9") (pin "1") (pinfunction "A_1") (pintype "passive"))
      (node (ref "U4") (pin "4") (pinfunction "VIN-_4") (pintype "input"))
    )
    (net (code "37") (name "Net-(C6-B)") (class "Default")
      (node (ref "C6") (pin "2") (pinfunction "B_2") (pintype "passive"))
      (node (ref "R6") (pin "1") (pinfunction "A_1") (pintype "passive"))
      (node (ref "R9") (pin "2") (pinfunction "B_2") (pintype "passive"))
      (node (ref "U4") (pin "1") (pinfunction "VOUT_1") (pintype "output"))
    )
    (net (code "38") (name "Net-(C7-A)") (class "Default")
      (node (ref "C7") (pin "1") (pinfunction "A_1") (pintype "passive"))
      (node (ref "R5") (pin "2") (pinfunction "B_2") (pintype "passive"))
      (node (ref "R8") (pin "1") (pinfunction "A_1") (pintype "passive"))
      (node (ref "U2") (pin "4") (pinfunction "VIN-_4") (pintype "input"))
    )
    (net (code "39") (name "Net-(C8-A)") (class "Default")
      (node (ref "C8") (pin "1") (pinfunction "A_1") (pintype "passive"))
      (node (ref "R13") (pin "1") (pinfunction "A_1") (pintype "passive"))
      (node (ref "U7") (pin "2") (pinfunction "TRIG_2") (pintype "passive"))
      (node (ref "U7") (pin "6") (pinfunction "THRES_6") (pintype "passive"))
    )
    (net (code "40") (name "Net-(C9-A)") (class "Default")
      (node (ref "C9") (pin "1") (pinfunction "A_1") (pintype "passive"))
      (node (ref "U7") (pin "5") (pinfunction "CONT_5") (pintype "passive"))
    )
    (net (code "41") (name "Net-(C10-A)") (class "Default")
      (node (ref "C10") (pin "1") (pinfunction "A_1") (pintype "passive"))
      (node (ref "C15") (pin "1") (pinfunction "A_1") (pintype "passive"))
      (node (ref "U11") (pin "3") (pinfunction "VIN_3") (pintype "passive"))
      (node (ref "U12") (pin "8") (pinfunction "V+_8") (pintype "passive"))
      (node (ref "U13") (pin "3") (pinfunction "VOUT_3") (pintype "passive"))
      (node (ref "U14") (pin "3") (pinfunction "VIN_3") (pintype "passive"))
    )
    (net (code "42") (name "Net-(C12-A)") (class "Default")
      (node (ref "C12") (pin "1") (pinfunction "A_1") (pintype "passive"))
      (node (ref "U12") (pin "2") (pinfunction "CAP+_2") (pintype "passive"))
    )
    (net (code "43") (name "Net-(C12-B)") (class "Default")
      (node (ref "C12") (pin "2") (pinfunction "B_2") (pintype "passive"))
      (node (ref "U12") (pin "4") (pinfunction "CAP-_4") (pintype "passive"))
    )
    (net (code "44") (name "Net-(C26-A)") (class "Default")
      (node (ref "C26") (pin "1") (pinfunction "A_1") (pintype "passive"))
      (node (ref "FB1") (pin "2") (pinfunction "B_2") (pintype "passive"))
      (node (ref "USB") (pin "1") (pinfunction "VBUS_1") (pintype "passive"))
    )
    (net (code "45") (name "Net-(C27-A)") (class "Default")
      (node (ref "C27") (pin "1") (pinfunction "A_1") (pintype "passive"))
      (node (ref "R78") (pin "1") (pinfunction "A_1") (pintype "passive"))
      (node (ref "USB") (pin "2") (pinfunction "D-_2") (pintype "passive"))
    )
    (net (code "46") (name "Net-(C28-A)") (class "Default")
      (node (ref "C28") (pin "1") (pinfunction "A_1") (pintype "passive"))
      (node (ref "R79") (pin "1") (pinfunction "A_1") (pintype "passive"))
      (node (ref "USB") (pin "3") (pinfunction "D+_3") (pintype "passive"))
    )
    (net (code "47") (name "Net-(C29-A)") (class "Default")
      (node (ref "C29") (pin "1") (pinfunction "A_1") (pintype "passive"))
      (node (ref "FB1") (pin "1") (pinfunction "A_1") (pintype "passive"))
      (node (ref "U9") (pin "12") (pinfunction "VCC_12") (pintype "power_in"))
    )
    (net (code "48") (name "Net-(C30-A)") (class "Default")
      (node (ref "C30") (pin "1") (pinfunction "A_1") (pintype "passive"))
      (node (ref "U9") (pin "16") (pinfunction "CBUS3_16") (pintype "passive"))
    )
    (net (code "49") (name "Net-(C36-A)") (class "Default")
      (node (ref "C36") (pin "1") (pinfunction "A_1") (pintype "passive"))
      (node (ref "C37") (pin "1") (pinfunction "A_1") (pintype "passive"))
      (node (ref "FB2") (pin "1") (pinfunction "A_1") (pintype "passive"))
      (node (ref "U1") (pin "13") (pinfunction "VDDA_13") (pintype "power_in"))
    )
    (net (code "50") (name "Net-(GreenLED1-PadC)") (class "Default")
      (node (ref "GreenLED1") (pin "C") (pinfunction "C_C") (pintype "passive"))
      (node (ref "GreenLED2") (pin "A") (pinfunction "A_A") (pintype "passive"))
    )
    (net (code "51") (name "Net-(GreenLED2-PadC)") (class "Default")
      (node (ref "GreenLED2") (pin "C") (pinfunction "C_C") (pintype "passive"))
      (node (ref "GreenLED3") (pin "A") (pinfunction "A_A") (pintype "passive"))
    )
    (net (code "52") (name "Net-(GreenLED3-PadC)") (class "Default")
      (node (ref "GreenLED3") (pin "C") (pinfunction "C_C") (pintype "passive"))
      (node (ref "GreenLED4") (pin "A") (pinfunction "A_A") (pintype "passive"))
    )
    (net (code "53") (name "Net-(GreenLED4-PadC)") (class "Default")
      (node (ref "GreenLED4") (pin "C") (pinfunction "C_C") (pintype "passive"))
      (node (ref "GreenLED5") (pin "A") (pinfunction "A_A") (pintype "passive"))
    )
    (net (code "54") (name "Net-(GreenLED5-PadC)") (class "Default")
      (node (ref "GreenLED5") (pin "C") (pinfunction "C_C") (pintype "passive"))
      (node (ref "GreenLED6") (pin "A") (pinfunction "A_A") (pintype "passive"))
    )
    (net (code "55") (name "Net-(GreenLED6-PadC)") (class "Default")
      (node (ref "GreenLED6") (pin "C") (pinfunction "C_C") (pintype "passive"))
      (node (ref "GreenLED7") (pin "A") (pinfunction "A_A") (pintype "passive"))
    )
    (net (code "56") (name "Net-(GreenLED7-PadC)") (class "Default")
      (node (ref "GreenLED7") (pin "C") (pinfunction "C_C") (pintype "passive"))
      (node (ref "GreenLED8") (pin "A") (pinfunction "A_A") (pintype "passive"))
    )
    (net (code "57") (name "Net-(GreenLED8-PadC)") (class "Default")
      (node (ref "GreenLED8") (pin "C") (pinfunction "C_C") (pintype "passive"))
      (node (ref "GreenLED9") (pin "A") (pinfunction "A_A") (pintype "passive"))
    )
    (net (code "58") (name "Net-(GreenLED10-PadA)") (class "Default")
      (node (ref "GreenLED10") (pin "A") (pinfunction "A_A") (pintype "passive"))
      (node (ref "GreenLED9") (pin "C") (pinfunction "C_C") (pintype "passive"))
    )
    (net (code "59") (name "Net-(R1-A)") (class "Default")
      (node (ref "R1") (pin "1") (pinfunction "A_1") (pintype "passive"))
      (node (ref "RedLED10") (pin "C") (pinfunction "C_C") (pintype "passive"))
    )
    (net (code "60") (name "Net-(R1-B)") (class "Default")
      (node (ref "Q1") (pin "D") (pinfunction "D_D") (pintype "passive"))
      (node (ref "R1") (pin "2") (pinfunction "B_2") (pintype "passive"))
    )
    (net (code "61") (name "Net-(R2-A)") (class "Default")
      (node (ref "BlueLED10") (pin "C") (pinfunction "C_C") (pintype "passive"))
      (node (ref "BlueLED5") (pin "C") (pinfunction "C_C") (pintype "passive"))
      (node (ref "R2") (pin "1") (pinfunction "A_1") (pintype "passive"))
    )
    (net (code "62") (name "Net-(R2-B)") (class "Default")
      (node (ref "Q2") (pin "D") (pinfunction "D_D") (pintype "passive"))
      (node (ref "R2") (pin "2") (pinfunction "B_2") (pintype "passive"))
    )
    (net (code "63") (name "Net-(R3-A)") (class "Default")
      (node (ref "D1") (pin "C") (pinfunction "C_C") (pintype "passive"))
      (node (ref "R3") (pin "1") (pinfunction "A_1") (pintype "passive"))
    )
    (net (code "64") (name "Net-(R4-A)") (class "Default")
      (node (ref "GreenLED10") (pin "C") (pinfunction "C_C") (pintype "passive"))
      (node (ref "R4") (pin "1") (pinfunction "A_1") (pintype "passive"))
    )
    (net (code "65") (name "Net-(R4-B)") (class "Default")
      (node (ref "Q4") (pin "D") (pinfunction "D_D") (pintype "passive"))
      (node (ref "R4") (pin "2") (pinfunction "B_2") (pintype "passive"))
    )
    (net (code "66") (name "Net-(R5-A)") (class "Default")
      (node (ref "D2") (pin "C") (pinfunction "C_C") (pintype "passive"))
      (node (ref "R5") (pin "1") (pinfunction "A_1") (pintype "passive"))
    )
    (net (code "67") (name "Net-(R10-A)") (class "Default")
      (node (ref "D3") (pin "A") (pinfunction "A_A") (pintype "passive"))
      (node (ref "R10") (pin "1") (pinfunction "A_1") (pintype "passive"))
      (node (ref "R6") (pin "2") (pinfunction "B_2") (pintype "passive"))
      (node (ref "U3") (pin "4") (pinfunction "VIN-_4") (pintype "input"))
    )
    (net (code "68") (name "Net-(R10-B)") (class "Default")
      (node (ref "D2") (pin "A") (pinfunction "A_A") (pintype "passive"))
      (node (ref "D3") (pin "C") (pinfunction "C_C") (pintype "passive"))
      (node (ref "R10") (pin "2") (pinfunction "B_2") (pintype "passive"))
      (node (ref "U3") (pin "1") (pinfunction "VOUT_1") (pintype "output"))
    )
    (net (code "69") (name "Net-(R11-B)") (class "Default")
      (node (ref "R11") (pin "2") (pinfunction "B_2") (pintype "passive"))
      (node (ref "R13") (pin "2") (pinfunction "B_2") (pintype "passive"))
      (node (ref "U7") (pin "7") (pinfunction "DISCH_7") (pintype "passive"))
    )
    (net (code "70") (name "Net-(R12-A)") (class "Default")
      (node (ref "Q3") (pin "D") (pinfunction "D_D") (pintype "passive"))
      (node (ref "R12") (pin "1") (pinfunction "A_1") (pintype "passive"))
    )
    (net (code "71") (name "Net-(R12-B)") (class "Default")
      (node (ref "LED1") (pin "C") (pinfunction "C_C") (pintype "passive"))
      (node (ref "R12") (pin "2") (pinfunction "B_2") (pintype "passive"))
    )
    (net (code "72") (name "Net-(R68-A)") (class "Default")
      (node (ref "R68") (pin "1") (pinfunction "A_1") (pintype "passive"))
      (node (ref "TE") (pin "C") (pinfunction "C_C") (pintype "passive"))
    )
    (net (code "73") (name "Net-(R71-A)") (class "Default")
      (node (ref "R71") (pin "1") (pinfunction "A_1") (pintype "passive"))
      (node (ref "SBUS1") (pin "1") (pinfunction "1_1") (pintype "passive"))
      (node (ref "U6") (pin "7") (pinfunction "B/Z_7") (pintype "bidirectional"))
    )
    (net (code "74") (name "Net-(R71-B)") (class "Default")
      (node (ref "R71") (pin "2") (pinfunction "B_2") (pintype "passive"))
      (node (ref "SBUS1") (pin "2") (pinfunction "2_2") (pintype "passive"))
      (node (ref "U6") (pin "6") (pinfunction "A/Y_6") (pintype "bidirectional"))
    )
    (net (code "75") (name "Net-(R76-B)") (class "Default")
      (node (ref "R76") (pin "2") (pinfunction "B_2") (pintype "passive"))
      (node (ref "URX") (pin "A") (pinfunction "A_A") (pintype "passive"))
    )
    (net (code "76") (name "Net-(R77-B)") (class "Default")
      (node (ref "R77") (pin "2") (pinfunction "B_2") (pintype "passive"))
      (node (ref "UTX") (pin "A") (pinfunction "A_A") (pintype "passive"))
    )
    (net (code "77") (name "Net-(R78-B)") (class "Default")
      (node (ref "R78") (pin "2") (pinfunction "B_2") (pintype "passive"))
      (node (ref "U9") (pin "9") (pinfunction "USBDM_9") (pintype "passive"))
    )
    (net (code "78") (name "Net-(R79-B)") (class "Default")
      (node (ref "R79") (pin "2") (pinfunction "B_2") (pintype "passive"))
      (node (ref "U9") (pin "8") (pinfunction "USBDP_8") (pintype "passive"))
    )
    (net (code "79") (name "Net-(R96-B)") (class "Default")
      (node (ref "R96") (pin "2") (pinfunction "B_2") (pintype "passive"))
      (node (ref "RX") (pin "A") (pinfunction "A_A") (pintype "passive"))
    )
    (net (code "80") (name "Net-(R97-B)") (class "Default")
      (node (ref "R97") (pin "2") (pinfunction "B_2") (pintype "passive"))
      (node (ref "TX") (pin "A") (pinfunction "A_A") (pintype "passive"))
    )
    (net (code "81") (name "Net-(RedLED1-PadC)") (class "Default")
      (node (ref "RedLED1") (pin "C") (pinfunction "C_C") (pintype "passive"))
      (node (ref "RedLED2") (pin "A") (pinfunction "A_A") (pintype "passive"))
    )
    (net (code "82") (name "Net-(RedLED2-PadC)") (class "Default")
      (node (ref "RedLED2") (pin "C") (pinfunction "C_C") (pintype "passive"))
      (node (ref "RedLED3") (pin "A") (pinfunction "A_A") (pintype "passive"))
    )
    (net (code "83") (name "Net-(RedLED3-PadC)") (class "Default")
      (node (ref "RedLED3") (pin "C") (pinfunction "C_C") (pintype "passive"))
      (node (ref "RedLED4") (pin "A") (pinfunction "A_A") (pintype "passive"))
    )
    (net (code "84") (name "Net-(RedLED4-PadC)") (class "Default")
      (node (ref "RedLED4") (pin "C") (pinfunction "C_C") (pintype "passive"))
      (node (ref "RedLED5") (pin "A") (pinfunction "A_A") (pintype "passive"))
    )
    (net (code "85") (name "Net-(RedLED5-PadC)") (class "Default")
      (node (ref "RedLED5") (pin "C") (pinfunction "C_C") (pintype "passive"))
      (node (ref "RedLED6") (pin "A") (pinfunction "A_A") (pintype "passive"))
    )
    (net (code "86") (name "Net-(RedLED6-PadC)") (class "Default")
      (node (ref "RedLED6") (pin "C") (pinfunction "C_C") (pintype "passive"))
      (node (ref "RedLED7") (pin "A") (pinfunction "A_A") (pintype "passive"))
    )
    (net (code "87") (name "Net-(RedLED7-PadC)") (class "Default")
      (node (ref "RedLED7") (pin "C") (pinfunction "C_C") (pintype "passive"))
      (node (ref "RedLED8") (pin "A") (pinfunction "A_A") (pintype "passive"))
    )
    (net (code "88") (name "Net-(RedLED8-PadC)") (class "Default")
      (node (ref "RedLED8") (pin "C") (pinfunction "C_C") (pintype "passive"))
      (node (ref "RedLED9") (pin "A") (pinfunction "A_A") (pintype "passive"))
    )
    (net (code "89") (name "Net-(RedLED10-PadA)") (class "Default")
      (node (ref "RedLED10") (pin "A") (pinfunction "A_A") (pintype "passive"))
      (node (ref "RedLED9") (pin "C") (pinfunction "C_C") (pintype "passive"))
    )
    (net (code "90") (name "Net-(U7-OUT)") (class "Default")
      (node (ref "Q3") (pin "G") (pinfunction "G_G") (pintype "passive"))
      (node (ref "U7") (pin "3") (pinfunction "OUT_3") (pintype "passive"))
    )
    (net (code "91") (name "Net-(U9-CBUS1)") (class "Default")
      (node (ref "U9") (pin "14") (pinfunction "CBUS1_14") (pintype "passive"))
      (node (ref "URX") (pin "C") (pinfunction "C_C") (pintype "passive"))
    )
    (net (code "92") (name "Net-(U9-CBUS2)") (class "Default")
      (node (ref "U9") (pin "7") (pinfunction "CBUS2_7") (pintype "passive"))
      (node (ref "UTX") (pin "C") (pinfunction "C_C") (pintype "passive"))
    )
    (net (code "93") (name "U3V3") (class "Default")
      (node (ref "C31") (pin "1") (pinfunction "A_1") (pintype "passive"))
      (node (ref "R76") (pin "1") (pinfunction "A_1") (pintype "passive"))
      (node (ref "R77") (pin "1") (pinfunction "A_1") (pintype "passive"))
      (node (ref "U9") (pin "10") (pinfunction "3V3OUT_10") (pintype "passive"))
      (node (ref "U9") (pin "11") (pinfunction "RESET#_11") (pintype "passive"))
      (node (ref "U9") (pin "3") (pinfunction "VCCIO_3") (pintype "power_in"))
    )
    (net (code "94") (name "unconnected-(U1B-PA5-Pad21)") (class "Default")
      (node (ref "U1") (pin "21") (pinfunction "PA5_21") (pintype "passive"))
    )
    (net (code "95") (name "unconnected-(U1B-PA6-Pad22)") (class "Default")
      (node (ref "U1") (pin "22") (pinfunction "PA6_22") (pintype "passive"))
    )
    (net (code "96") (name "unconnected-(U1B-PA7-Pad23)") (class "Default")
      (node (ref "U1") (pin "23") (pinfunction "PA7_23") (pintype "passive"))
    )
    (net (code "97") (name "unconnected-(U1B-PA8-Pad41)") (class "Default")
      (node (ref "U1") (pin "41") (pinfunction "PA8_41") (pintype "passive"))
    )
    (net (code "98") (name "unconnected-(U1B-PA13-Pad46)") (class "Default")
      (node (ref "U1") (pin "46") (pinfunction "PA13_46") (pintype "passive"))
    )
    (net (code "99") (name "unconnected-(U1B-PA14-Pad49)") (class "Default")
      (node (ref "U1") (pin "49") (pinfunction "PA14_49") (pintype "passive"))
    )
    (net (code "100") (name "unconnected-(U1B-PA15-Pad50)") (class "Default")
      (node (ref "U1") (pin "50") (pinfunction "PA15_50") (pintype "passive"))
    )
    (net (code "101") (name "unconnected-(U1B-PB0-Pad26)") (class "Default")
      (node (ref "U1") (pin "26") (pinfunction "PB0_26") (pintype "passive"))
    )
    (net (code "102") (name "unconnected-(U1B-PB1-Pad27)") (class "Default")
      (node (ref "U1") (pin "27") (pinfunction "PB1_27") (pintype "passive"))
    )
    (net (code "103") (name "unconnected-(U1B-PB2{slash}BOOT1-Pad28)") (class "Default")
      (node (ref "U1") (pin "28") (pinfunction "PB2/BOOT1_28") (pintype "passive"))
    )
    (net (code "104") (name "unconnected-(U1B-PB3-Pad55)") (class "Default")
      (node (ref "U1") (pin "55") (pinfunction "PB3_55") (pintype "passive"))
    )
    (net (code "105") (name "unconnected-(U1B-PB4-Pad56)") (class "Default")
      (node (ref "U1") (pin "56") (pinfunction "PB4_56") (pintype "passive"))
    )
    (net (code "106") (name "unconnected-(U1B-PB5-Pad57)") (class "Default")
      (node (ref "U1") (pin "57") (pinfunction "PB5_57") (pintype "passive"))
    )
    (net (code "107") (name "unconnected-(U1B-PB6-Pad58)") (class "Default")
      (node (ref "U1") (pin "58") (pinfunction "PB6_58") (pintype "passive"))
    )
    (net (code "108") (name "unconnected-(U1B-PB7-Pad59)") (class "Default")
      (node (ref "U1") (pin "59") (pinfunction "PB7_59") (pintype "passive"))
    )
    (net (code "109") (name "unconnected-(U1B-PB8-Pad61)") (class "Default")
      (node (ref "U1") (pin "61") (pinfunction "PB8_61") (pintype "passive"))
    )
    (net (code "110") (name "unconnected-(U1B-PB9-Pad62)") (class "Default")
      (node (ref "U1") (pin "62") (pinfunction "PB9_62") (pintype "passive"))
    )
    (net (code "111") (name "unconnected-(U1B-PB12-Pad33)") (class "Default")
      (node (ref "U1") (pin "33") (pinfunction "PB12_33") (pintype "passive"))
    )
    (net (code "112") (name "unconnected-(U1B-PB13-Pad34)") (class "Default")
      (node (ref "U1") (pin "34") (pinfunction "PB13_34") (pintype "passive"))
    )
    (net (code "113") (name "unconnected-(U1B-PB14-Pad35)") (class "Default")
      (node (ref "U1") (pin "35") (pinfunction "PB14_35") (pintype "passive"))
    )
    (net (code "114") (name "unconnected-(U1B-PB15-Pad36)") (class "Default")
      (node (ref "U1") (pin "36") (pinfunction "PB15_36") (pintype "passive"))
    )
    (net (code "115") (name "unconnected-(U1B-PC3-Pad11)") (class "Default")
      (node (ref "U1") (pin "11") (pinfunction "PC3_11") (pintype "passive"))
    )
    (net (code "116") (name "unconnected-(U1B-PC4-Pad24)") (class "Default")
      (node (ref "U1") (pin "24") (pinfunction "PC4_24") (pintype "passive"))
    )
    (net (code "117") (name "unconnected-(U1B-PC5-Pad25)") (class "Default")
      (node (ref "U1") (pin "25") (pinfunction "PC5_25") (pintype "passive"))
    )
    (net (code "118") (name "unconnected-(U1B-PC6-Pad37)") (class "Default")
      (node (ref "U1") (pin "37") (pinfunction "PC6_37") (pintype "passive"))
    )
    (net (code "119") (name "unconnected-(U1B-PC7-Pad38)") (class "Default")
      (node (ref "U1") (pin "38") (pinfunction "PC7_38") (pintype "passive"))
    )
    (net (code "120") (name "unconnected-(U1B-PC8-Pad39)") (class "Default")
      (node (ref "U1") (pin "39") (pinfunction "PC8_39") (pintype "passive"))
    )
    (net (code "121") (name "unconnected-(U1B-PC9-Pad40)") (class "Default")
      (node (ref "U1") (pin "40") (pinfunction "PC9_40") (pintype "passive"))
    )
    (net (code "122") (name "unconnected-(U1B-PC10-Pad51)") (class "Default")
      (node (ref "U1") (pin "51") (pinfunction "PC10_51") (pintype "passive"))
    )
    (net (code "123") (name "unconnected-(U1B-PC11-Pad52)") (class "Default")
      (node (ref "U1") (pin "52") (pinfunction "PC11_52") (pintype "passive"))
    )
    (net (code "124") (name "unconnected-(U1B-PC13-Pad2)") (class "Default")
      (node (ref "U1") (pin "2") (pinfunction "PC13_2") (pintype "passive"))
    )
    (net (code "125") (name "unconnected-(U1B-PC14-Pad3)") (class "Default")
      (node (ref "U1") (pin "3") (pinfunction "PC14_3") (pintype "passive"))
    )
    (net (code "126") (name "unconnected-(U1B-PC15-Pad4)") (class "Default")
      (node (ref "U1") (pin "4") (pinfunction "PC15_4") (pintype "passive"))
    )
    (net (code "127") (name "unconnected-(U5-2IN+-Pad5)") (class "Default")
      (node (ref "U5") (pin "5") (pinfunction "2IN+_5") (pintype "passive"))
    )
    (net (code "128") (name "unconnected-(U5-2IN--Pad6)") (class "Default")
      (node (ref "U5") (pin "6") (pinfunction "2IN-_6") (pintype "passive"))
    )
    (net (code "129") (name "unconnected-(U5-2OUT-Pad7)") (class "Default")
      (node (ref "U5") (pin "7") (pinfunction "2OUT_7") (pintype "passive"))
    )
    (net (code "130") (name "unconnected-(U8-INT1-Pad7)") (class "Default")
      (node (ref "U8") (pin "7") (pinfunction "INT1_7") (pintype "passive"))
    )
    (net (code "131") (name "unconnected-(U9-CBUS0-Pad15)") (class "Default")
      (node (ref "U9") (pin "15") (pinfunction "CBUS0_15") (pintype "passive"))
    )
    (net (code "132") (name "unconnected-(U12-LV-Pad6)") (class "Default")
      (node (ref "U12") (pin "6") (pinfunction "LV_6") (pintype "passive"))
    )
    (net (code "133") (name "unconnected-(U12-OSC-Pad7)") (class "Default")
      (node (ref "U12") (pin "7") (pinfunction "OSC_7") (pintype "passive"))
    )
    (net (code "134") (name "unconnected-(USB-ID-Pad4)") (class "Default")
      (node (ref "USB") (pin "4") (pinfunction "ID_4") (pintype "passive"))
    )
  )
)
